# noise-fob-no-fill.net
KiCad netlist of a schematic drawn in EAGLE
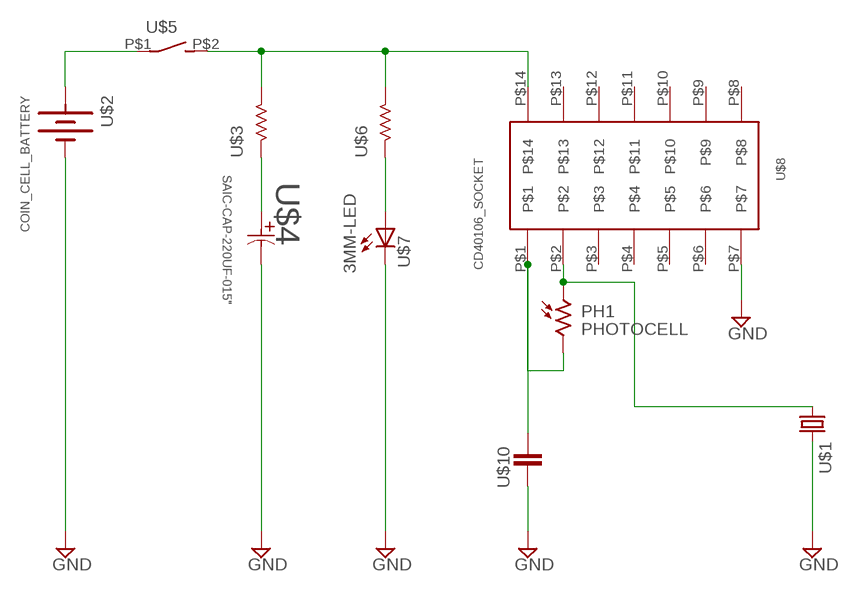
[diagram p0: schematic, sheet 1]

(export (version "E")
  (design (tool "Eeschema 10.0.6"))
  (components
    (comp (ref "PH1")
      (value "PHOTOCELL")
      (footprint "eagle-import:PHOTOCELL")
      (libsource (lib "eagle-import") (part "PHOTOCELL"))
    )
    (comp (ref "U$1")
      (value "PIEZO_BUZZER_2")
      (footprint "eagle-import:PIEZO_BUZZER_2")
      (libsource (lib "eagle-import") (part "PIEZO_BUZZER_2"))
    )
    (comp (ref "U$2")
      (value "COIN_CELL_BATTERY")
      (footprint "eagle-import:COIN_BATTERY")
      (libsource (lib "eagle-import") (part "COIN_CELL_BATTERY"))
    )
    (comp (ref "U$3")
      (value "RESISTOR-1/4W-THROUGH-HOLE")
      (footprint "eagle-import:1_4W_TH_RESISTOR")
      (libsource (lib "eagle-import") (part "RESISTOR-1/4W-THROUGH-HOLE"))
    )
    (comp (ref "U$4")
      (value "SAIC-CAP-220UF-015\"")
      (footprint "eagle-import:SAIC-CAP-0.15_-LEAD-SPACING-01")
      (libsource (lib "eagle-import") (part "SAIC-CAP-220UF-015{dblquote}"))
    )
    (comp (ref "U$5")
      (value "TACTILE_SWITCH")
      (footprint "eagle-import:TACTILE_SWITCH")
      (libsource (lib "eagle-import") (part "TACTILE_SWITCH"))
    )
    (comp (ref "U$6")
      (value "RESISTOR-1/4W-THROUGH-HOLE")
      (footprint "eagle-import:1_4W_TH_RESISTOR")
      (libsource (lib "eagle-import") (part "RESISTOR-1/4W-THROUGH-HOLE"))
    )
    (comp (ref "U$7")
      (value "3MM-LED")
      (footprint "eagle-import:LED3MM")
      (libsource (lib "eagle-import") (part "3MM-LED"))
    )
    (comp (ref "U$8")
      (value "CD40106_SOCKET")
      (footprint "eagle-import:DIP_14_SOCKET")
      (libsource (lib "eagle-import") (part "CD40106_SOCKET"))
    )
    (comp (ref "U$10")
      (value "SAIC-CAP-0.1UF-02\"")
      (footprint "eagle-import:SAIC-CAP-0.2_-LEAD-SPACING-03")
      (libsource (lib "eagle-import") (part "SAIC-CAP-0.1UF-02{dblquote}"))
    )
  )
  (nets
    (net (code "1") (name "GND") (class "Default")
      (node (ref "U$1") (pin "P$2") (pinfunction "2_P$2") (pintype "passive"))
      (node (ref "U$10") (pin "P$1") (pinfunction "1_P$1") (pintype "passive"))
      (node (ref "U$2") (pin "P$2") (pinfunction "-_P$2") (pintype "power_in"))
      (node (ref "U$4") (pin "P$2") (pinfunction "22_P$2") (pintype "passive"))
      (node (ref "U$7") (pin "K") (pinfunction "2_K") (pintype "output"))
      (node (ref "U$8") (pin "P$7") (pinfunction "P$7_P$7") (pintype "bidirectional"))
    )
    (net (code "2") (name "Net-(PH1-1)") (class "Default")
      (node (ref "PH1") (pin "P$1") (pinfunction "1_P$1") (pintype "passive"))
      (node (ref "U$1") (pin "P$1") (pinfunction "1_P$1") (pintype "passive"))
      (node (ref "U$8") (pin "P$2") (pinfunction "P$2_P$2") (pintype "bidirectional"))
    )
    (net (code "3") (name "Net-(PH1-2)") (class "Default")
      (node (ref "PH1") (pin "P$2") (pinfunction "2_P$2") (pintype "passive"))
      (node (ref "U$10") (pin "P$2") (pinfunction "2_P$2") (pintype "passive"))
      (node (ref "U$8") (pin "P$1") (pinfunction "P$1_P$1") (pintype "bidirectional"))
    )
    (net (code "4") (name "Net-(U$2-+)") (class "Default")
      (node (ref "U$2") (pin "P$1") (pinfunction "+_P$1") (pintype "power_in"))
      (node (ref "U$5") (pin "P$1") (pinfunction "P_P$1") (pintype "passive"))
    )
    (net (code "5") (name "Net-(U$4-11)") (class "Default")
      (node (ref "U$3") (pin "P$1") (pinfunction "P$1_P$1") (pintype "bidirectional"))
      (node (ref "U$4") (pin "P$1") (pinfunction "11_P$1") (pintype "passive"))
    )
    (net (code "6") (name "Net-(U$5-S)") (class "Default")
      (node (ref "U$3") (pin "P$2") (pinfunction "P$2_P$2") (pintype "bidirectional"))
      (node (ref "U$5") (pin "P$2") (pinfunction "S_P$2") (pintype "passive"))
      (node (ref "U$6") (pin "P$2") (pinfunction "P$2_P$2") (pintype "bidirectional"))
      (node (ref "U$8") (pin "P$14") (pinfunction "P$14_P$14") (pintype "bidirectional"))
    )
    (net (code "7") (name "Net-(U$7-1)") (class "Default")
      (node (ref "U$6") (pin "P$1") (pinfunction "P$1_P$1") (pintype "bidirectional"))
      (node (ref "U$7") (pin "A") (pinfunction "1_A") (pintype "input"))
    )
    (net (code "8") (name "unconnected-(U$8-PadP$3)") (class "Default")
      (node (ref "U$8") (pin "P$3") (pinfunction "P$3_P$3") (pintype "bidirectional"))
    )
    (net (code "9") (name "unconnected-(U$8-PadP$4)") (class "Default")
      (node (ref "U$8") (pin "P$4") (pinfunction "P$4_P$4") (pintype "bidirectional"))
    )
    (net (code "10") (name "unconnected-(U$8-PadP$5)") (class "Default")
      (node (ref "U$8") (pin "P$5") (pinfunction "P$5_P$5") (pintype "bidirectional"))
    )
    (net (code "11") (name "unconnected-(U$8-PadP$6)") (class "Default")
      (node (ref "U$8") (pin "P$6") (pinfunction "P$6_P$6") (pintype "bidirectional"))
    )
    (net (code "12") (name "unconnected-(U$8-PadP$8)") (class "Default")
      (node (ref "U$8") (pin "P$8") (pinfunction "P$8_P$8") (pintype "bidirectional"))
    )
    (net (code "13") (name "unconnected-(U$8-PadP$9)") (class "Default")
      (node (ref "U$8") (pin "P$9") (pinfunction "P$9_P$9") (pintype "bidirectional"))
    )
    (net (code "14") (name "unconnected-(U$8-PadP$10)") (class "Default")
      (node (ref "U$8") (pin "P$10") (pinfunction "P$10_P$10") (pintype "bidirectional"))
    )
    (net (code "15") (name "unconnected-(U$8-PadP$11)") (class "Default")
      (node (ref "U$8") (pin "P$11") (pinfunction "P$11_P$11") (pintype "bidirectional"))
    )
    (net (code "16") (name "unconnected-(U$8-PadP$12)") (class "Default")
      (node (ref "U$8") (pin "P$12") (pinfunction "P$12_P$12") (pintype "bidirectional"))
    )
    (net (code "17") (name "unconnected-(U$8-PadP$13)") (class "Default")
      (node (ref "U$8") (pin "P$13") (pinfunction "P$13_P$13") (pintype "bidirectional"))
    )
  )
)
